# main.net
KiCad netlist of a schematic drawn in Altium Designer
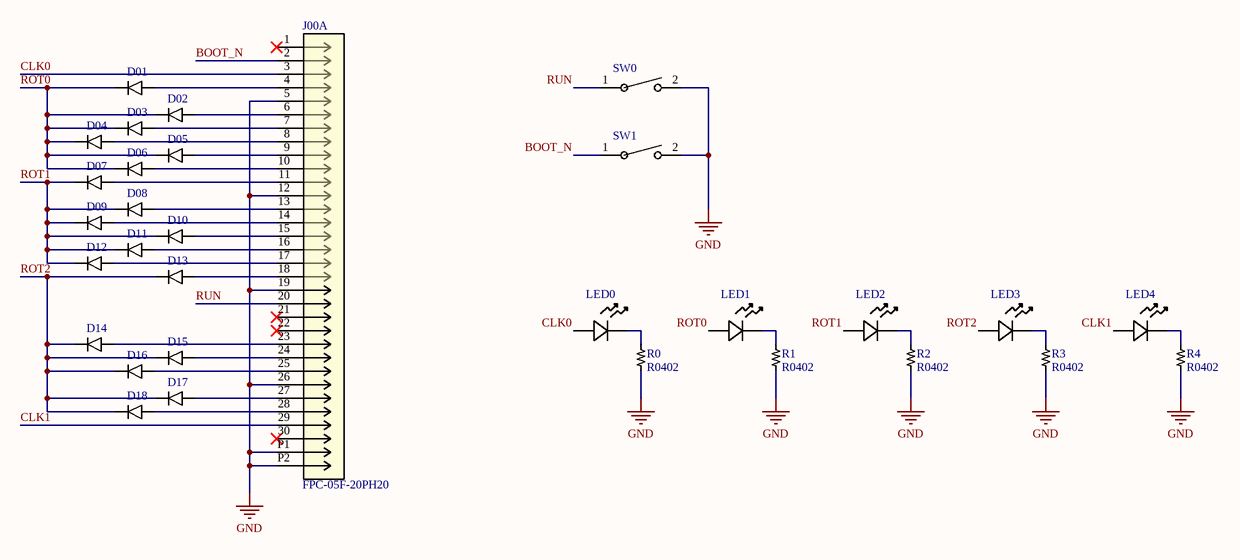
[diagram p0: main.SchDoc]

(export (version "E")
  (design (tool "Eeschema 10.0.6"))
  (components
    (comp (ref "D01")
      (value "1N4148W")
      (footprint "SOD123_DIO")
      (description "Small Signal Diode")
      (libsource (lib "Cornix_Library") (part "1N4148W"))
    )
    (comp (ref "D02")
      (value "1N4148W")
      (footprint "SOD123_DIO")
      (description "Small Signal Diode")
      (libsource (lib "Cornix_Library") (part "1N4148W"))
    )
    (comp (ref "D03")
      (value "1N4148W")
      (footprint "SOD123_DIO")
      (description "Small Signal Diode")
      (libsource (lib "Cornix_Library") (part "1N4148W"))
    )
    (comp (ref "D04")
      (value "1N4148W")
      (footprint "SOD123_DIO")
      (description "Small Signal Diode")
      (libsource (lib "Cornix_Library") (part "1N4148W"))
    )
    (comp (ref "D05")
      (value "1N4148W")
      (footprint "SOD123_DIO")
      (description "Small Signal Diode")
      (libsource (lib "Cornix_Library") (part "1N4148W"))
    )
    (comp (ref "D06")
      (value "1N4148W")
      (footprint "SOD123_DIO")
      (description "Small Signal Diode")
      (libsource (lib "Cornix_Library") (part "1N4148W"))
    )
    (comp (ref "D07")
      (value "1N4148W")
      (footprint "SOD123_DIO")
      (description "Small Signal Diode")
      (libsource (lib "Cornix_Library") (part "1N4148W"))
    )
    (comp (ref "D08")
      (value "1N4148W")
      (footprint "SOD123_DIO")
      (description "Small Signal Diode")
      (libsource (lib "Cornix_Library") (part "1N4148W"))
    )
    (comp (ref "D09")
      (value "1N4148W")
      (footprint "SOD123_DIO")
      (description "Small Signal Diode")
      (libsource (lib "Cornix_Library") (part "1N4148W"))
    )
    (comp (ref "D10")
      (value "1N4148W")
      (footprint "SOD123_DIO")
      (description "Small Signal Diode")
      (libsource (lib "Cornix_Library") (part "1N4148W"))
    )
    (comp (ref "D11")
      (value "1N4148W")
      (footprint "SOD123_DIO")
      (description "Small Signal Diode")
      (libsource (lib "Cornix_Library") (part "1N4148W"))
    )
    (comp (ref "D12")
      (value "1N4148W")
      (footprint "SOD123_DIO")
      (description "Small Signal Diode")
      (libsource (lib "Cornix_Library") (part "1N4148W"))
    )
    (comp (ref "D13")
      (value "1N4148W")
      (footprint "SOD123_DIO")
      (description "Small Signal Diode")
      (libsource (lib "Cornix_Library") (part "1N4148W"))
    )
    (comp (ref "D14")
      (value "1N4148W")
      (footprint "SOD123_DIO")
      (description "Small Signal Diode")
      (libsource (lib "Cornix_Library") (part "1N4148W"))
    )
    (comp (ref "D15")
      (value "1N4148W")
      (footprint "SOD123_DIO")
      (description "Small Signal Diode")
      (libsource (lib "Cornix_Library") (part "1N4148W"))
    )
    (comp (ref "D16")
      (value "1N4148W")
      (footprint "SOD123_DIO")
      (description "Small Signal Diode")
      (libsource (lib "Cornix_Library") (part "1N4148W"))
    )
    (comp (ref "D17")
      (value "1N4148W")
      (footprint "SOD123_DIO")
      (description "Small Signal Diode")
      (libsource (lib "Cornix_Library") (part "1N4148W"))
    )
    (comp (ref "D18")
      (value "1N4148W")
      (footprint "SOD123_DIO")
      (description "Small Signal Diode")
      (libsource (lib "Cornix_Library") (part "1N4148W"))
    )
    (comp (ref "J00A")
      (value "FPC-05F-20PH20")
      (footprint "FPC-05F-30PH20")
      (description "30 Pin 0.5 Pitch FPC connector")
      (libsource (lib "Cornix_Library") (part "FPC-05F-30PH20"))
    )
    (comp (ref "LED0")
      (value "XL-1608UWC-04")
      (footprint "LED_XL-1608_XLG")
      (description "No Description Available")
      (fields (field (name "COPYRIGHT") "Copyright (C) 2025 Ultra Librarian. All rights reserved."))
      (libsource (lib "Cornix_Library") (part "XL-1608UWC-04"))
    )
    (comp (ref "LED1")
      (value "XL-1608UWC-04")
      (footprint "LED_XL-1608_XLG")
      (description "No Description Available")
      (fields (field (name "COPYRIGHT") "Copyright (C) 2025 Ultra Librarian. All rights reserved."))
      (libsource (lib "Cornix_Library") (part "XL-1608UWC-04"))
    )
    (comp (ref "LED2")
      (value "XL-1608UWC-04")
      (footprint "LED_XL-1608_XLG")
      (description "No Description Available")
      (fields (field (name "COPYRIGHT") "Copyright (C) 2025 Ultra Librarian. All rights reserved."))
      (libsource (lib "Cornix_Library") (part "XL-1608UWC-04"))
    )
    (comp (ref "LED3")
      (value "XL-1608UWC-04")
      (footprint "LED_XL-1608_XLG")
      (description "No Description Available")
      (fields (field (name "COPYRIGHT") "Copyright (C) 2025 Ultra Librarian. All rights reserved."))
      (libsource (lib "Cornix_Library") (part "XL-1608UWC-04"))
    )
    (comp (ref "LED4")
      (value "XL-1608UWC-04")
      (footprint "LED_XL-1608_XLG")
      (description "No Description Available")
      (fields (field (name "COPYRIGHT") "Copyright (C) 2025 Ultra Librarian. All rights reserved."))
      (libsource (lib "Cornix_Library") (part "XL-1608UWC-04"))
    )
    (comp (ref "R0")
      (value "R0402")
      (footprint "RES0402_CPF_TYCO_TYC")
      (description "CPF 0402 RL")
      (fields
        (field (name "MANUFACTURER_PART_NUMBER") "CPF0402B33RE1")
        (field (name "COPYRIGHT") "Copyright (C) 2025 Ultra Librarian. All rights reserved.")
      )
      (libsource (lib "Cornix_Library") (part "R0402"))
    )
    (comp (ref "R1")
      (value "R0402")
      (footprint "RES0402_CPF_TYCO_TYC")
      (description "CPF 0402 RL")
      (fields
        (field (name "MANUFACTURER_PART_NUMBER") "CPF0402B33RE1")
        (field (name "COPYRIGHT") "Copyright (C) 2025 Ultra Librarian. All rights reserved.")
      )
      (libsource (lib "Cornix_Library") (part "R0402"))
    )
    (comp (ref "R2")
      (value "R0402")
      (footprint "RES0402_CPF_TYCO_TYC")
      (description "CPF 0402 RL")
      (fields
        (field (name "MANUFACTURER_PART_NUMBER") "CPF0402B33RE1")
        (field (name "COPYRIGHT") "Copyright (C) 2025 Ultra Librarian. All rights reserved.")
      )
      (libsource (lib "Cornix_Library") (part "R0402"))
    )
    (comp (ref "R3")
      (value "R0402")
      (footprint "RES0402_CPF_TYCO_TYC")
      (description "CPF 0402 RL")
      (fields
        (field (name "MANUFACTURER_PART_NUMBER") "CPF0402B33RE1")
        (field (name "COPYRIGHT") "Copyright (C) 2025 Ultra Librarian. All rights reserved.")
      )
      (libsource (lib "Cornix_Library") (part "R0402"))
    )
    (comp (ref "R4")
      (value "R0402")
      (footprint "RES0402_CPF_TYCO_TYC")
      (description "CPF 0402 RL")
      (fields
        (field (name "MANUFACTURER_PART_NUMBER") "CPF0402B33RE1")
        (field (name "COPYRIGHT") "Copyright (C) 2025 Ultra Librarian. All rights reserved.")
      )
      (libsource (lib "Cornix_Library") (part "R0402"))
    )
    (comp (ref "SW0")
      (value "TS-1088-AR02016")
      (footprint "SW_TS-1088_XNP")
      (description "Description")
      (fields (field (name "COPYRIGHT") "Copyright (C) 2026 Ultra Librarian. All rights reserved."))
      (libsource (lib "Cornix_Library") (part "TS-1088-AR02016"))
    )
    (comp (ref "SW1")
      (value "TS-1088-AR02016")
      (footprint "SW_TS-1088_XNP")
      (description "Description")
      (fields (field (name "COPYRIGHT") "Copyright (C) 2026 Ultra Librarian. All rights reserved."))
      (libsource (lib "Cornix_Library") (part "TS-1088-AR02016"))
    )
  )
  (nets
    (net (code "1") (name "/BOOT_N") (class "Default")
      (node (ref "J00A") (pin "2") (pinfunction "2_2") (pintype "passive"))
      (node (ref "SW1") (pin "1") (pinfunction "1_1") (pintype "passive"))
    )
    (net (code "2") (name "/CLK0") (class "Default")
      (node (ref "J00A") (pin "3") (pinfunction "3_3") (pintype "passive"))
      (node (ref "LED0") (pin "2") (pinfunction "ANODE_2") (pintype "passive"))
    )
    (net (code "3") (name "/CLK1") (class "Default")
      (node (ref "J00A") (pin "29") (pinfunction "29_29") (pintype "passive"))
      (node (ref "LED4") (pin "2") (pinfunction "ANODE_2") (pintype "passive"))
    )
    (net (code "4") (name "/ROT0") (class "Default")
      (node (ref "D01") (pin "K") (pinfunction "K_K") (pintype "passive"))
      (node (ref "D02") (pin "K") (pinfunction "K_K") (pintype "passive"))
      (node (ref "D03") (pin "K") (pinfunction "K_K") (pintype "passive"))
      (node (ref "D04") (pin "K") (pinfunction "K_K") (pintype "passive"))
      (node (ref "D05") (pin "K") (pinfunction "K_K") (pintype "passive"))
      (node (ref "D06") (pin "K") (pinfunction "K_K") (pintype "passive"))
      (node (ref "LED1") (pin "2") (pinfunction "ANODE_2") (pintype "passive"))
    )
    (net (code "5") (name "/ROT1") (class "Default")
      (node (ref "D07") (pin "K") (pinfunction "K_K") (pintype "passive"))
      (node (ref "D08") (pin "K") (pinfunction "K_K") (pintype "passive"))
      (node (ref "D09") (pin "K") (pinfunction "K_K") (pintype "passive"))
      (node (ref "D10") (pin "K") (pinfunction "K_K") (pintype "passive"))
      (node (ref "D11") (pin "K") (pinfunction "K_K") (pintype "passive"))
      (node (ref "D12") (pin "K") (pinfunction "K_K") (pintype "passive"))
      (node (ref "LED2") (pin "2") (pinfunction "ANODE_2") (pintype "passive"))
    )
    (net (code "6") (name "/ROT2") (class "Default")
      (node (ref "D13") (pin "K") (pinfunction "K_K") (pintype "passive"))
      (node (ref "D14") (pin "K") (pinfunction "K_K") (pintype "passive"))
      (node (ref "D15") (pin "K") (pinfunction "K_K") (pintype "passive"))
      (node (ref "D16") (pin "K") (pinfunction "K_K") (pintype "passive"))
      (node (ref "D17") (pin "K") (pinfunction "K_K") (pintype "passive"))
      (node (ref "D18") (pin "K") (pinfunction "K_K") (pintype "passive"))
      (node (ref "LED3") (pin "2") (pinfunction "ANODE_2") (pintype "passive"))
    )
    (net (code "7") (name "/RUN") (class "Default")
      (node (ref "J00A") (pin "20") (pinfunction "20_20") (pintype "passive"))
      (node (ref "SW0") (pin "1") (pinfunction "1_1") (pintype "passive"))
    )
    (net (code "8") (name "GND") (class "Default")
      (node (ref "J00A") (pin "12") (pinfunction "12_12") (pintype "passive"))
      (node (ref "J00A") (pin "19") (pinfunction "19_19") (pintype "passive"))
      (node (ref "J00A") (pin "26") (pinfunction "26_26") (pintype "passive"))
      (node (ref "J00A") (pin "5") (pinfunction "5_5") (pintype "passive"))
      (node (ref "J00A") (pin "P1") (pinfunction "P1_P1") (pintype "passive"))
      (node (ref "J00A") (pin "P2") (pinfunction "P2_P2") (pintype "passive"))
      (node (ref "R0") (pin "2") (pinfunction "2_2") (pintype "passive"))
      (node (ref "R1") (pin "2") (pinfunction "2_2") (pintype "passive"))
      (node (ref "R2") (pin "2") (pinfunction "2_2") (pintype "passive"))
      (node (ref "R3") (pin "2") (pinfunction "2_2") (pintype "passive"))
      (node (ref "R4") (pin "2") (pinfunction "2_2") (pintype "passive"))
      (node (ref "SW0") (pin "2") (pinfunction "2_2") (pintype "passive"))
      (node (ref "SW1") (pin "2") (pinfunction "2_2") (pintype "passive"))
    )
    (net (code "9") (name "Net-(D01-PadA)") (class "Default")
      (node (ref "D01") (pin "A") (pinfunction "A_A") (pintype "passive"))
      (node (ref "J00A") (pin "4") (pinfunction "4_4") (pintype "passive"))
    )
    (net (code "10") (name "Net-(D02-PadA)") (class "Default")
      (node (ref "D02") (pin "A") (pinfunction "A_A") (pintype "passive"))
      (node (ref "J00A") (pin "6") (pinfunction "6_6") (pintype "passive"))
    )
    (net (code "11") (name "Net-(D03-PadA)") (class "Default")
      (node (ref "D03") (pin "A") (pinfunction "A_A") (pintype "passive"))
      (node (ref "J00A") (pin "7") (pinfunction "7_7") (pintype "passive"))
    )
    (net (code "12") (name "Net-(D04-PadA)") (class "Default")
      (node (ref "D04") (pin "A") (pinfunction "A_A") (pintype "passive"))
      (node (ref "J00A") (pin "8") (pinfunction "8_8") (pintype "passive"))
    )
    (net (code "13") (name "Net-(D05-PadA)") (class "Default")
      (node (ref "D05") (pin "A") (pinfunction "A_A") (pintype "passive"))
      (node (ref "J00A") (pin "9") (pinfunction "9_9") (pintype "passive"))
    )
    (net (code "14") (name "Net-(D06-PadA)") (class "Default")
      (node (ref "D06") (pin "A") (pinfunction "A_A") (pintype "passive"))
      (node (ref "J00A") (pin "10") (pinfunction "10_10") (pintype "passive"))
    )
    (net (code "15") (name "Net-(D07-PadA)") (class "Default")
      (node (ref "D07") (pin "A") (pinfunction "A_A") (pintype "passive"))
      (node (ref "J00A") (pin "11") (pinfunction "11_11") (pintype "passive"))
    )
    (net (code "16") (name "Net-(D08-PadA)") (class "Default")
      (node (ref "D08") (pin "A") (pinfunction "A_A") (pintype "passive"))
      (node (ref "J00A") (pin "13") (pinfunction "13_13") (pintype "passive"))
    )
    (net (code "17") (name "Net-(D09-PadA)") (class "Default")
      (node (ref "D09") (pin "A") (pinfunction "A_A") (pintype "passive"))
      (node (ref "J00A") (pin "14") (pinfunction "14_14") (pintype "passive"))
    )
    (net (code "18") (name "Net-(D10-PadA)") (class "Default")
      (node (ref "D10") (pin "A") (pinfunction "A_A") (pintype "passive"))
      (node (ref "J00A") (pin "15") (pinfunction "15_15") (pintype "passive"))
    )
    (net (code "19") (name "Net-(D11-PadA)") (class "Default")
      (node (ref "D11") (pin "A") (pinfunction "A_A") (pintype "passive"))
      (node (ref "J00A") (pin "16") (pinfunction "16_16") (pintype "passive"))
    )
    (net (code "20") (name "Net-(D12-PadA)") (class "Default")
      (node (ref "D12") (pin "A") (pinfunction "A_A") (pintype "passive"))
      (node (ref "J00A") (pin "17") (pinfunction "17_17") (pintype "passive"))
    )
    (net (code "21") (name "Net-(D13-PadA)") (class "Default")
      (node (ref "D13") (pin "A") (pinfunction "A_A") (pintype "passive"))
      (node (ref "J00A") (pin "18") (pinfunction "18_18") (pintype "passive"))
    )
    (net (code "22") (name "Net-(D14-PadA)") (class "Default")
      (node (ref "D14") (pin "A") (pinfunction "A_A") (pintype "passive"))
      (node (ref "J00A") (pin "23") (pinfunction "23_23") (pintype "passive"))
    )
    (net (code "23") (name "Net-(D15-PadA)") (class "Default")
      (node (ref "D15") (pin "A") (pinfunction "A_A") (pintype "passive"))
      (node (ref "J00A") (pin "24") (pinfunction "24_24") (pintype "passive"))
    )
    (net (code "24") (name "Net-(D16-PadA)") (class "Default")
      (node (ref "D16") (pin "A") (pinfunction "A_A") (pintype "passive"))
      (node (ref "J00A") (pin "25") (pinfunction "25_25") (pintype "passive"))
    )
    (net (code "25") (name "Net-(D17-PadA)") (class "Default")
      (node (ref "D17") (pin "A") (pinfunction "A_A") (pintype "passive"))
      (node (ref "J00A") (pin "27") (pinfunction "27_27") (pintype "passive"))
    )
    (net (code "26") (name "Net-(D18-PadA)") (class "Default")
      (node (ref "D18") (pin "A") (pinfunction "A_A") (pintype "passive"))
      (node (ref "J00A") (pin "28") (pinfunction "28_28") (pintype "passive"))
    )
    (net (code "27") (name "Net-(LED0-CATHODE)") (class "Default")
      (node (ref "LED0") (pin "1") (pinfunction "CATHODE_1") (pintype "passive"))
      (node (ref "R0") (pin "1") (pinfunction "1_1") (pintype "passive"))
    )
    (net (code "28") (name "Net-(LED1-CATHODE)") (class "Default")
      (node (ref "LED1") (pin "1") (pinfunction "CATHODE_1") (pintype "passive"))
      (node (ref "R1") (pin "1") (pinfunction "1_1") (pintype "passive"))
    )
    (net (code "29") (name "Net-(LED2-CATHODE)") (class "Default")
      (node (ref "LED2") (pin "1") (pinfunction "CATHODE_1") (pintype "passive"))
      (node (ref "R2") (pin "1") (pinfunction "1_1") (pintype "passive"))
    )
    (net (code "30") (name "Net-(LED3-CATHODE)") (class "Default")
      (node (ref "LED3") (pin "1") (pinfunction "CATHODE_1") (pintype "passive"))
      (node (ref "R3") (pin "1") (pinfunction "1_1") (pintype "passive"))
    )
    (net (code "31") (name "Net-(LED4-CATHODE)") (class "Default")
      (node (ref "LED4") (pin "1") (pinfunction "CATHODE_1") (pintype "passive"))
      (node (ref "R4") (pin "1") (pinfunction "1_1") (pintype "passive"))
    )
    (net (code "32") (name "unconnected-(J00A-Pad1)") (class "Default")
      (node (ref "J00A") (pin "1") (pinfunction "1_1") (pintype "passive+no_connect"))
    )
    (net (code "33") (name "unconnected-(J00A-Pad21)") (class "Default")
      (node (ref "J00A") (pin "21") (pinfunction "21_21") (pintype "passive+no_connect"))
    )
    (net (code "34") (name "unconnected-(J00A-Pad22)") (class "Default")
      (node (ref "J00A") (pin "22") (pinfunction "22_22") (pintype "passive+no_connect"))
    )
    (net (code "35") (name "unconnected-(J00A-Pad30)") (class "Default")
      (node (ref "J00A") (pin "30") (pinfunction "30_30") (pintype "passive+no_connect"))
    )
  )
)
